# esp32_balance.net
KiCad netlist of a schematic drawn in EAGLE
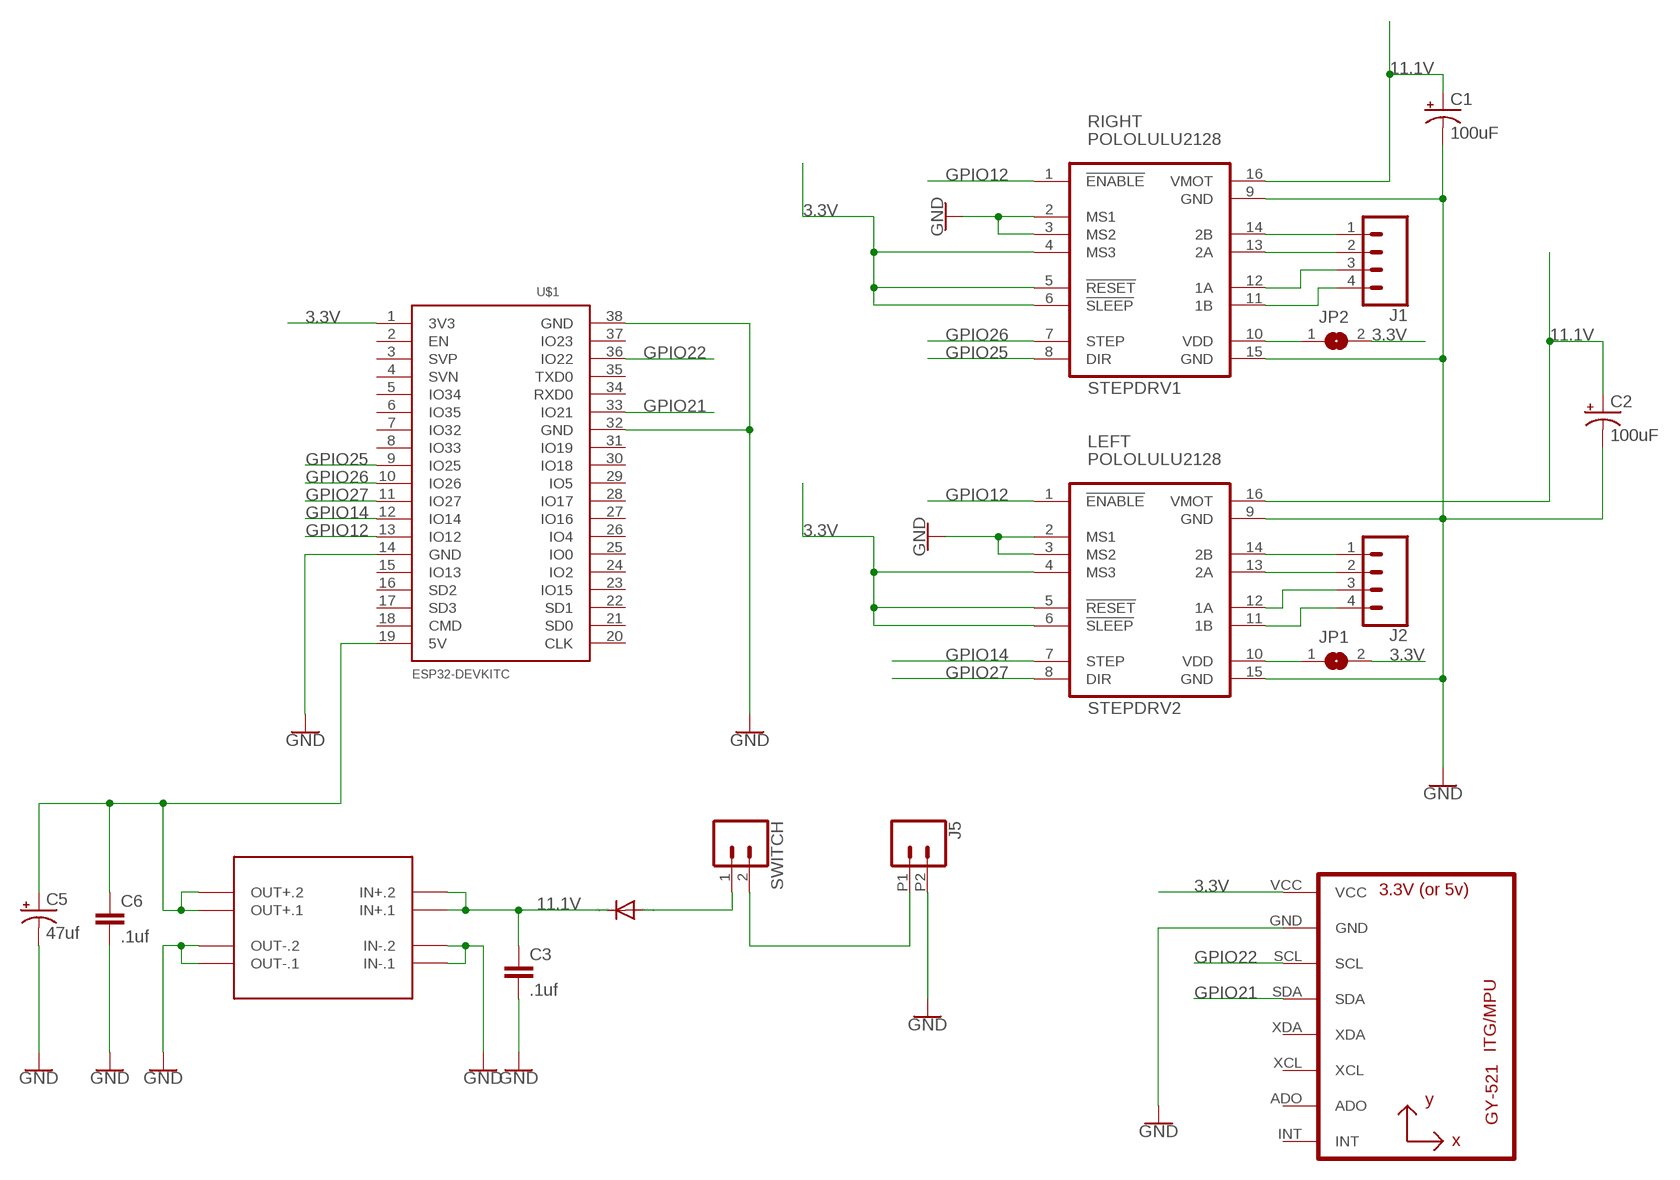
[diagram p0: schematic, sheet 1]

(export (version "E")
  (design (tool "Eeschema 10.0.6"))
  (components
    (comp (ref "C1")
      (value "100uF")
      (footprint "eagle-import:CPOL-RADIAL-2.5MM-6.5MM")
      (libsource (lib "eagle-import") (part "100UF-POLAR-RADIAL-2.5MM-25V-20%"))
    )
    (comp (ref "C2")
      (value "100uF")
      (footprint "eagle-import:CPOL-RADIAL-2.5MM-6.5MM")
      (libsource (lib "eagle-import") (part "100UF-POLAR-RADIAL-2.5MM-25V-20%"))
    )
    (comp (ref "C3")
      (value ".1uf")
      (footprint "eagle-import:CAP-PTH-2.54")
      (libsource (lib "eagle-import") (part "22PF-PTH-2.54MM-200V-5%"))
    )
    (comp (ref "C5")
      (value "47uf")
      (footprint "eagle-import:CPOL-RADIAL-2.5MM-6.5MM")
      (libsource (lib "eagle-import") (part "100UF-POLAR-RADIAL-2.5MM-25V-20%"))
    )
    (comp (ref "C6")
      (value ".1uf")
      (footprint "eagle-import:CAP-PTH-2.54")
      (libsource (lib "eagle-import") (part "22PF-PTH-2.54MM-200V-5%"))
    )
    (comp (ref "D1")
      (value "1N4004")
      (footprint "eagle-import:DO41-10")
      (libsource (lib "eagle-import") (part "1N4004"))
    )
    (comp (ref "J1")
      (value "CONN_04")
      (footprint "eagle-import:1X04")
      (libsource (lib "eagle-import") (part "CONN_04"))
    )
    (comp (ref "J2")
      (value "CONN_04")
      (footprint "eagle-import:1X04")
      (libsource (lib "eagle-import") (part "CONN_04"))
    )
    (comp (ref "J5")
      (value "CONN_022.54MM_SCREWTERM")
      (footprint "eagle-import:1X02_2.54_SCREWTERM")
      (libsource (lib "eagle-import") (part "CONN_022.54MM_SCREWTERM"))
    )
    (comp (ref "JP1")
      (value "SJW")
      (footprint "eagle-import:SJW")
      (libsource (lib "eagle-import") (part "SJW"))
    )
    (comp (ref "JP2")
      (value "SJW")
      (footprint "eagle-import:SJW")
      (libsource (lib "eagle-import") (part "SJW"))
    )
    (comp (ref "STEPDRV1")
      (value "POLOLULU2128")
      (footprint "eagle-import:POLOLULU2128")
      (libsource (lib "eagle-import") (part "POLOLULU2128"))
    )
    (comp (ref "STEPDRV2")
      (value "POLOLULU2128")
      (footprint "eagle-import:POLOLULU2128")
      (libsource (lib "eagle-import") (part "POLOLULU2128"))
    )
    (comp (ref "SWITCH")
      (value "CONN_02")
      (footprint "eagle-import:1X02")
      (libsource (lib "eagle-import") (part "CONN_02"))
    )
    (comp (ref "U$1")
      (value "ESP32DEVKITC")
      (footprint "eagle-import:ESP32-DEVKITC")
      (libsource (lib "eagle-import") (part "ESP32DEVKITC"))
    )
    (comp (ref "U$3")
      (value "DC-DC-STEP-DOWN-MP1584")
      (footprint "eagle-import:DC-DC-STEP-DOWN-MP1584")
      (libsource (lib "eagle-import") (part "DC-DC-STEP-DOWN-MP1584"))
    )
    (comp (ref "U1")
      (value "GY-521MPU6050")
      (footprint "eagle-import:GY-521")
      (libsource (lib "eagle-import") (part "GY-521MPU6050"))
    )
  )
  (nets
    (net (code "1") (name "/3.3V") (class "Default")
      (node (ref "JP1") (pin "2") (pinfunction "2_2") (pintype "passive"))
      (node (ref "JP2") (pin "2") (pinfunction "2_2") (pintype "passive"))
      (node (ref "STEPDRV1") (pin "4") (pinfunction "MS3_4") (pintype "input"))
      (node (ref "STEPDRV1") (pin "5") (pinfunction "~{RESET}_5") (pintype "input"))
      (node (ref "STEPDRV1") (pin "6") (pinfunction "~{SLEEP}_6") (pintype "input"))
      (node (ref "STEPDRV2") (pin "4") (pinfunction "MS3_4") (pintype "input"))
      (node (ref "STEPDRV2") (pin "5") (pinfunction "~{RESET}_5") (pintype "input"))
      (node (ref "STEPDRV2") (pin "6") (pinfunction "~{SLEEP}_6") (pintype "input"))
      (node (ref "U$1") (pin "1") (pinfunction "3V3_1") (pintype "bidirectional"))
      (node (ref "U1") (pin "VCC") (pinfunction "VCC_VCC") (pintype "bidirectional"))
    )
    (net (code "2") (name "/11.1V") (class "Default")
      (node (ref "C1") (pin "1") (pinfunction "+_1") (pintype "passive"))
      (node (ref "C2") (pin "1") (pinfunction "+_1") (pintype "passive"))
      (node (ref "C3") (pin "1") (pinfunction "1_1") (pintype "passive"))
      (node (ref "D1") (pin "C") (pinfunction "C_C") (pintype "passive"))
      (node (ref "STEPDRV1") (pin "16") (pinfunction "VMOT_16") (pintype "power_in"))
      (node (ref "STEPDRV2") (pin "16") (pinfunction "VMOT_16") (pintype "power_in"))
      (node (ref "U$3") (pin "IN+.1") (pinfunction "IN+.1_IN+.1") (pintype "bidirectional"))
      (node (ref "U$3") (pin "IN+.2") (pinfunction "IN+.2_IN+.2") (pintype "bidirectional"))
    )
    (net (code "3") (name "/GPIO12") (class "Default")
      (node (ref "STEPDRV1") (pin "1") (pinfunction "~{ENABLE}_1") (pintype "input"))
      (node (ref "STEPDRV2") (pin "1") (pinfunction "~{ENABLE}_1") (pintype "input"))
      (node (ref "U$1") (pin "13") (pinfunction "IO12_13") (pintype "bidirectional"))
    )
    (net (code "4") (name "/GPIO14") (class "Default")
      (node (ref "STEPDRV2") (pin "7") (pinfunction "STEP_7") (pintype "input"))
      (node (ref "U$1") (pin "12") (pinfunction "IO14_12") (pintype "bidirectional"))
    )
    (net (code "5") (name "/GPIO21") (class "Default")
      (node (ref "U$1") (pin "33") (pinfunction "IO21_33") (pintype "bidirectional"))
      (node (ref "U1") (pin "SDA") (pinfunction "SDA_SDA") (pintype "bidirectional"))
    )
    (net (code "6") (name "/GPIO22") (class "Default")
      (node (ref "U$1") (pin "36") (pinfunction "IO22_36") (pintype "bidirectional"))
      (node (ref "U1") (pin "SCL") (pinfunction "SCL_SCL") (pintype "bidirectional"))
    )
    (net (code "7") (name "/GPIO25") (class "Default")
      (node (ref "STEPDRV1") (pin "8") (pinfunction "DIR_8") (pintype "input"))
      (node (ref "U$1") (pin "9") (pinfunction "IO25_9") (pintype "bidirectional"))
    )
    (net (code "8") (name "/GPIO26") (class "Default")
      (node (ref "STEPDRV1") (pin "7") (pinfunction "STEP_7") (pintype "input"))
      (node (ref "U$1") (pin "10") (pinfunction "IO26_10") (pintype "bidirectional"))
    )
    (net (code "9") (name "/GPIO27") (class "Default")
      (node (ref "STEPDRV2") (pin "8") (pinfunction "DIR_8") (pintype "input"))
      (node (ref "U$1") (pin "11") (pinfunction "IO27_11") (pintype "bidirectional"))
    )
    (net (code "10") (name "GND") (class "Default")
      (node (ref "C1") (pin "2") (pinfunction "-_2") (pintype "passive"))
      (node (ref "C2") (pin "2") (pinfunction "-_2") (pintype "passive"))
      (node (ref "C3") (pin "2") (pinfunction "2_2") (pintype "passive"))
      (node (ref "C5") (pin "2") (pinfunction "-_2") (pintype "passive"))
      (node (ref "C6") (pin "2") (pinfunction "2_2") (pintype "passive"))
      (node (ref "J5") (pin "P2") (pinfunction "2_P2") (pintype "passive"))
      (node (ref "STEPDRV1") (pin "15") (pinfunction "GND_15") (pintype "power_in"))
      (node (ref "STEPDRV1") (pin "2") (pinfunction "MS1_2") (pintype "input"))
      (node (ref "STEPDRV1") (pin "3") (pinfunction "MS2_3") (pintype "input"))
      (node (ref "STEPDRV1") (pin "9") (pinfunction "GND_9") (pintype "power_in"))
      (node (ref "STEPDRV2") (pin "15") (pinfunction "GND_15") (pintype "power_in"))
      (node (ref "STEPDRV2") (pin "2") (pinfunction "MS1_2") (pintype "input"))
      (node (ref "STEPDRV2") (pin "3") (pinfunction "MS2_3") (pintype "input"))
      (node (ref "STEPDRV2") (pin "9") (pinfunction "GND_9") (pintype "power_in"))
      (node (ref "U$1") (pin "14") (pinfunction "GND_14") (pintype "bidirectional"))
      (node (ref "U$1") (pin "32") (pinfunction "GND_32") (pintype "bidirectional"))
      (node (ref "U$1") (pin "38") (pinfunction "GND_38") (pintype "bidirectional"))
      (node (ref "U$3") (pin "IN-.1") (pinfunction "IN-.1_IN-.1") (pintype "bidirectional"))
      (node (ref "U$3") (pin "IN-.2") (pinfunction "IN-.2_IN-.2") (pintype "bidirectional"))
      (node (ref "U$3") (pin "OUT-.1") (pinfunction "OUT-.1_OUT-.1") (pintype "bidirectional"))
      (node (ref "U$3") (pin "OUT-.2") (pinfunction "OUT-.2_OUT-.2") (pintype "bidirectional"))
      (node (ref "U1") (pin "GND") (pinfunction "GND_GND") (pintype "bidirectional"))
    )
    (net (code "11") (name "Net-(C5-+)") (class "Default")
      (node (ref "C5") (pin "1") (pinfunction "+_1") (pintype "passive"))
      (node (ref "C6") (pin "1") (pinfunction "1_1") (pintype "passive"))
      (node (ref "U$1") (pin "19") (pinfunction "5V_19") (pintype "bidirectional"))
      (node (ref "U$3") (pin "OUT+.1") (pinfunction "OUT+.1_OUT+.1") (pintype "bidirectional"))
      (node (ref "U$3") (pin "OUT+.2") (pinfunction "OUT+.2_OUT+.2") (pintype "bidirectional"))
    )
    (net (code "12") (name "Net-(D1-PadA)") (class "Default")
      (node (ref "D1") (pin "A") (pinfunction "A_A") (pintype "passive"))
      (node (ref "SWITCH") (pin "1") (pinfunction "1_1") (pintype "passive"))
    )
    (net (code "13") (name "Net-(J5-1)") (class "Default")
      (node (ref "J5") (pin "P1") (pinfunction "1_P1") (pintype "passive"))
      (node (ref "SWITCH") (pin "2") (pinfunction "2_2") (pintype "passive"))
    )
    (net (code "14") (name "Net-(STEPDRV1-1A)") (class "Default")
      (node (ref "J1") (pin "3") (pinfunction "3_3") (pintype "passive"))
      (node (ref "STEPDRV1") (pin "12") (pinfunction "1A_12") (pintype "output"))
    )
    (net (code "15") (name "Net-(STEPDRV1-1B)") (class "Default")
      (node (ref "J1") (pin "4") (pinfunction "4_4") (pintype "passive"))
      (node (ref "STEPDRV1") (pin "11") (pinfunction "1B_11") (pintype "output"))
    )
    (net (code "16") (name "Net-(STEPDRV1-2A)") (class "Default")
      (node (ref "J1") (pin "2") (pinfunction "2_2") (pintype "passive"))
      (node (ref "STEPDRV1") (pin "13") (pinfunction "2A_13") (pintype "output"))
    )
    (net (code "17") (name "Net-(STEPDRV1-2B)") (class "Default")
      (node (ref "J1") (pin "1") (pinfunction "1_1") (pintype "passive"))
      (node (ref "STEPDRV1") (pin "14") (pinfunction "2B_14") (pintype "output"))
    )
    (net (code "18") (name "Net-(STEPDRV1-VDD)") (class "Default")
      (node (ref "JP2") (pin "1") (pinfunction "1_1") (pintype "passive"))
      (node (ref "STEPDRV1") (pin "10") (pinfunction "VDD_10") (pintype "power_in"))
    )
    (net (code "19") (name "Net-(STEPDRV2-1A)") (class "Default")
      (node (ref "J2") (pin "3") (pinfunction "3_3") (pintype "passive"))
      (node (ref "STEPDRV2") (pin "12") (pinfunction "1A_12") (pintype "output"))
    )
    (net (code "20") (name "Net-(STEPDRV2-1B)") (class "Default")
      (node (ref "J2") (pin "4") (pinfunction "4_4") (pintype "passive"))
      (node (ref "STEPDRV2") (pin "11") (pinfunction "1B_11") (pintype "output"))
    )
    (net (code "21") (name "Net-(STEPDRV2-2A)") (class "Default")
      (node (ref "J2") (pin "2") (pinfunction "2_2") (pintype "passive"))
      (node (ref "STEPDRV2") (pin "13") (pinfunction "2A_13") (pintype "output"))
    )
    (net (code "22") (name "Net-(STEPDRV2-2B)") (class "Default")
      (node (ref "J2") (pin "1") (pinfunction "1_1") (pintype "passive"))
      (node (ref "STEPDRV2") (pin "14") (pinfunction "2B_14") (pintype "output"))
    )
    (net (code "23") (name "Net-(STEPDRV2-VDD)") (class "Default")
      (node (ref "JP1") (pin "1") (pinfunction "1_1") (pintype "passive"))
      (node (ref "STEPDRV2") (pin "10") (pinfunction "VDD_10") (pintype "power_in"))
    )
    (net (code "24") (name "unconnected-(U$1-CLK-Pad20)") (class "Default")
      (node (ref "U$1") (pin "20") (pinfunction "CLK_20") (pintype "bidirectional"))
    )
    (net (code "25") (name "unconnected-(U$1-CMD-Pad18)") (class "Default")
      (node (ref "U$1") (pin "18") (pinfunction "CMD_18") (pintype "bidirectional"))
    )
    (net (code "26") (name "unconnected-(U$1-EN-Pad2)") (class "Default")
      (node (ref "U$1") (pin "2") (pinfunction "EN_2") (pintype "bidirectional"))
    )
    (net (code "27") (name "unconnected-(U$1-IO0-Pad25)") (class "Default")
      (node (ref "U$1") (pin "25") (pinfunction "IO0_25") (pintype "bidirectional"))
    )
    (net (code "28") (name "unconnected-(U$1-IO2-Pad24)") (class "Default")
      (node (ref "U$1") (pin "24") (pinfunction "IO2_24") (pintype "bidirectional"))
    )
    (net (code "29") (name "unconnected-(U$1-IO4-Pad26)") (class "Default")
      (node (ref "U$1") (pin "26") (pinfunction "IO4_26") (pintype "bidirectional"))
    )
    (net (code "30") (name "unconnected-(U$1-IO5-Pad29)") (class "Default")
      (node (ref "U$1") (pin "29") (pinfunction "IO5_29") (pintype "bidirectional"))
    )
    (net (code "31") (name "unconnected-(U$1-IO13-Pad15)") (class "Default")
      (node (ref "U$1") (pin "15") (pinfunction "IO13_15") (pintype "bidirectional"))
    )
    (net (code "32") (name "unconnected-(U$1-IO15-Pad23)") (class "Default")
      (node (ref "U$1") (pin "23") (pinfunction "IO15_23") (pintype "bidirectional"))
    )
    (net (code "33") (name "unconnected-(U$1-IO16-Pad27)") (class "Default")
      (node (ref "U$1") (pin "27") (pinfunction "IO16_27") (pintype "bidirectional"))
    )
    (net (code "34") (name "unconnected-(U$1-IO17-Pad28)") (class "Default")
      (node (ref "U$1") (pin "28") (pinfunction "IO17_28") (pintype "bidirectional"))
    )
    (net (code "35") (name "unconnected-(U$1-IO18-Pad30)") (class "Default")
      (node (ref "U$1") (pin "30") (pinfunction "IO18_30") (pintype "bidirectional"))
    )
    (net (code "36") (name "unconnected-(U$1-IO19-Pad31)") (class "Default")
      (node (ref "U$1") (pin "31") (pinfunction "IO19_31") (pintype "bidirectional"))
    )
    (net (code "37") (name "unconnected-(U$1-IO23-Pad37)") (class "Default")
      (node (ref "U$1") (pin "37") (pinfunction "IO23_37") (pintype "bidirectional"))
    )
    (net (code "38") (name "unconnected-(U$1-IO32-Pad7)") (class "Default")
      (node (ref "U$1") (pin "7") (pinfunction "IO32_7") (pintype "bidirectional"))
    )
    (net (code "39") (name "unconnected-(U$1-IO33-Pad8)") (class "Default")
      (node (ref "U$1") (pin "8") (pinfunction "IO33_8") (pintype "bidirectional"))
    )
    (net (code "40") (name "unconnected-(U$1-IO34-Pad5)") (class "Default")
      (node (ref "U$1") (pin "5") (pinfunction "IO34_5") (pintype "bidirectional"))
    )
    (net (code "41") (name "unconnected-(U$1-IO35-Pad6)") (class "Default")
      (node (ref "U$1") (pin "6") (pinfunction "IO35_6") (pintype "bidirectional"))
    )
    (net (code "42") (name "unconnected-(U$1-RXD0-Pad34)") (class "Default")
      (node (ref "U$1") (pin "34") (pinfunction "RXD0_34") (pintype "bidirectional"))
    )
    (net (code "43") (name "unconnected-(U$1-SD0-Pad21)") (class "Default")
      (node (ref "U$1") (pin "21") (pinfunction "SD0_21") (pintype "bidirectional"))
    )
    (net (code "44") (name "unconnected-(U$1-SD1-Pad22)") (class "Default")
      (node (ref "U$1") (pin "22") (pinfunction "SD1_22") (pintype "bidirectional"))
    )
    (net (code "45") (name "unconnected-(U$1-SD2-Pad16)") (class "Default")
      (node (ref "U$1") (pin "16") (pinfunction "SD2_16") (pintype "bidirectional"))
    )
    (net (code "46") (name "unconnected-(U$1-SD3-Pad17)") (class "Default")
      (node (ref "U$1") (pin "17") (pinfunction "SD3_17") (pintype "bidirectional"))
    )
    (net (code "47") (name "unconnected-(U$1-SVN-Pad4)") (class "Default")
      (node (ref "U$1") (pin "4") (pinfunction "SVN_4") (pintype "bidirectional"))
    )
    (net (code "48") (name "unconnected-(U$1-SVP-Pad3)") (class "Default")
      (node (ref "U$1") (pin "3") (pinfunction "SVP_3") (pintype "bidirectional"))
    )
    (net (code "49") (name "unconnected-(U$1-TXD0-Pad35)") (class "Default")
      (node (ref "U$1") (pin "35") (pinfunction "TXD0_35") (pintype "bidirectional"))
    )
    (net (code "50") (name "unconnected-(U1-PadADO)") (class "Default")
      (node (ref "U1") (pin "ADO") (pinfunction "ADO_ADO") (pintype "bidirectional"))
    )
    (net (code "51") (name "unconnected-(U1-PadINT)") (class "Default")
      (node (ref "U1") (pin "INT") (pinfunction "INT_INT") (pintype "bidirectional"))
    )
    (net (code "52") (name "unconnected-(U1-PadXCL)") (class "Default")
      (node (ref "U1") (pin "XCL") (pinfunction "XCL_XCL") (pintype "bidirectional"))
    )
    (net (code "53") (name "unconnected-(U1-PadXDA)") (class "Default")
      (node (ref "U1") (pin "XDA") (pinfunction "XDA_XDA") (pintype "bidirectional"))
    )
  )
)
